# PR9013.net
KiCad netlist of a schematic drawn in EAGLE
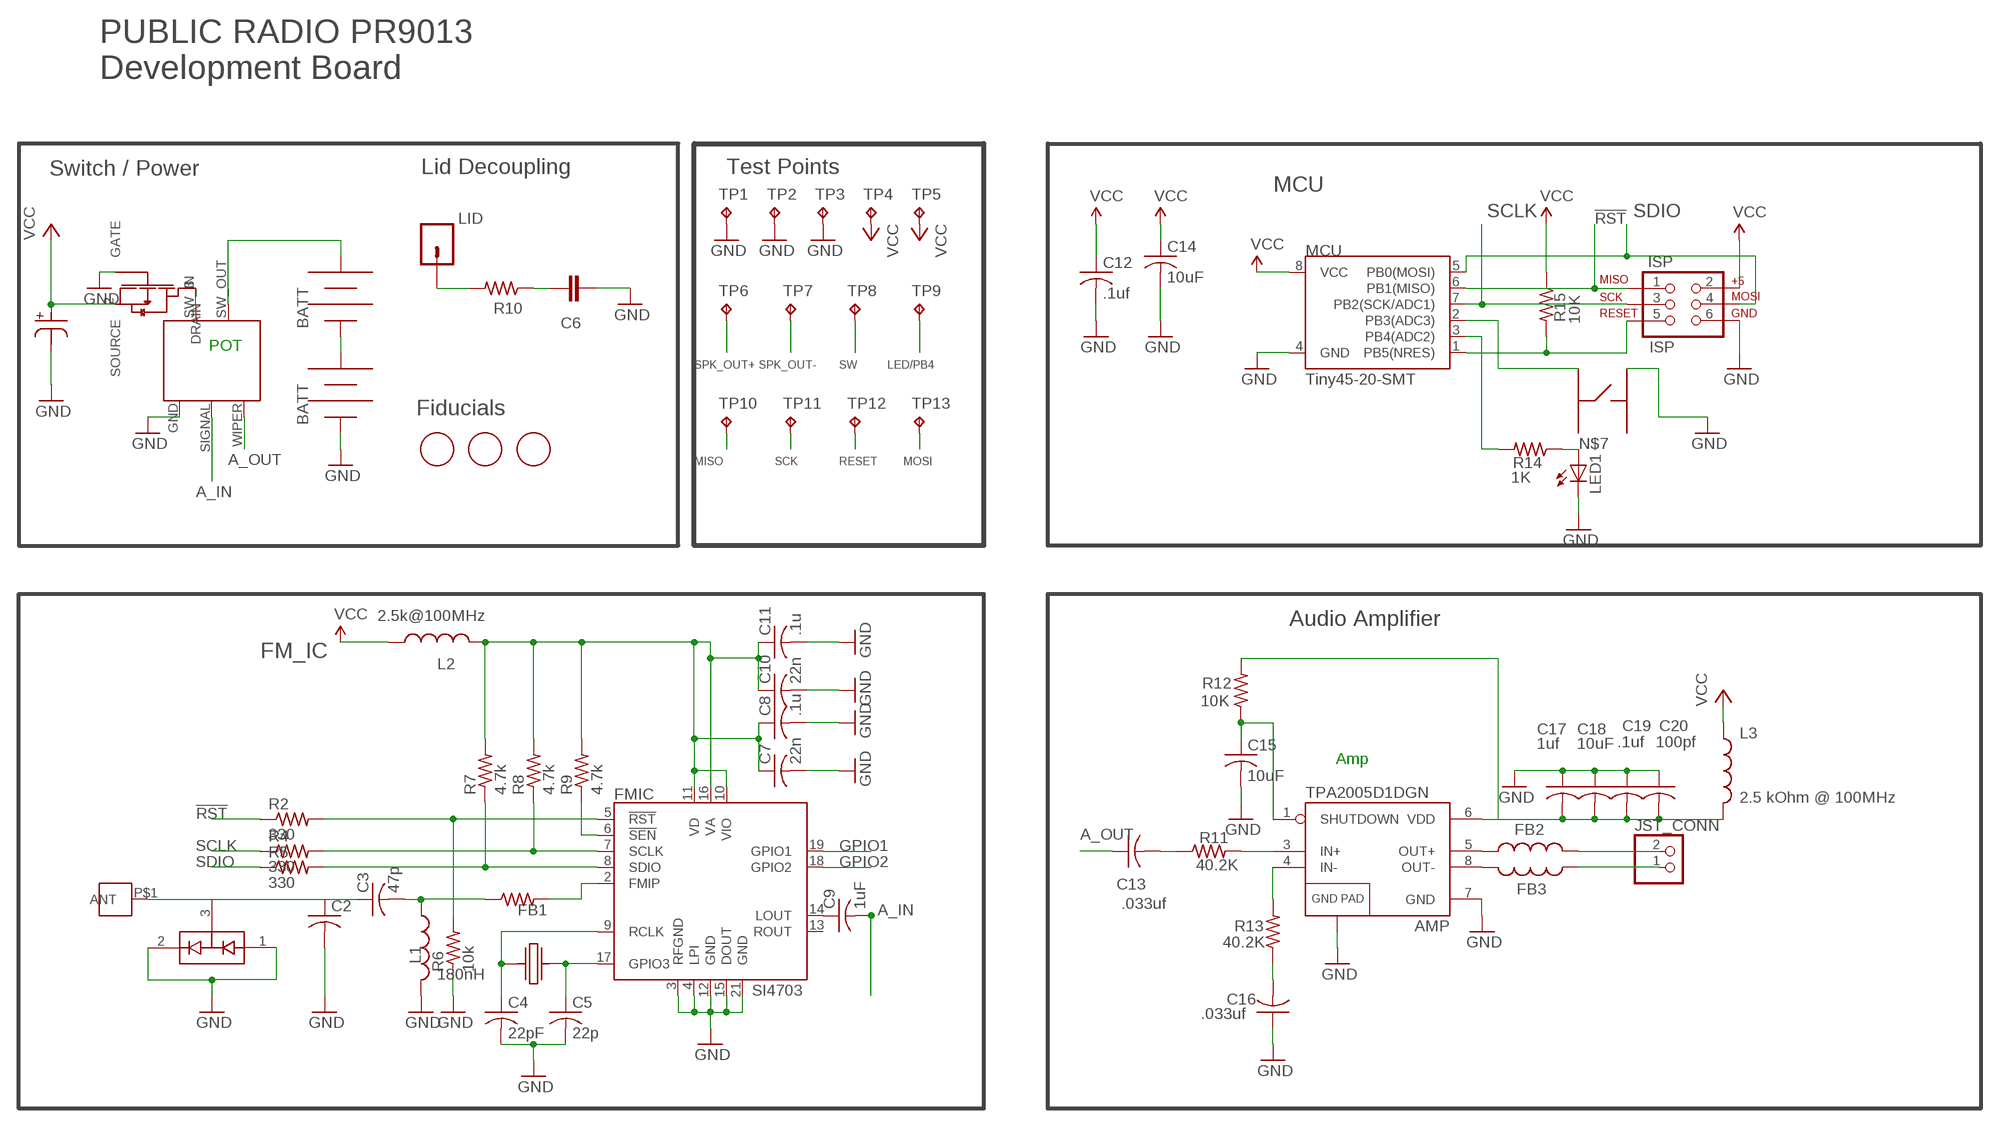
[diagram p0: schematic, sheet 1]

(export (version "E")
  (design (tool "Eeschema 10.0.6"))
  (components
    (comp (ref "AMP")
      (value "TPA2005D1DGN")
      (footprint "eagle-import:POWER-SOP8")
      (libsource (lib "eagle-import") (part "TPA2005D1DGN"))
    )
    (comp (ref "C1")
      (value "220uF")
      (footprint "eagle-import:NICHICON_SERIESUD")
      (libsource (lib "eagle-import") (part "NICHICON_SERIESUD"))
    )
    (comp (ref "C2")
      (value "C-USC0402")
      (footprint "eagle-import:C0402")
      (libsource (lib "eagle-import") (part "C-USC0402"))
    )
    (comp (ref "C3")
      (value "47p")
      (footprint "eagle-import:C0402")
      (libsource (lib "eagle-import") (part "C-USC0402"))
    )
    (comp (ref "C4")
      (value "22pF")
      (footprint "eagle-import:C0402")
      (libsource (lib "eagle-import") (part "C-USC0402"))
    )
    (comp (ref "C5")
      (value "22p")
      (footprint "eagle-import:C0402")
      (libsource (lib "eagle-import") (part "C-USC0402"))
    )
    (comp (ref "C6")
      (value "CAP0805")
      (footprint "eagle-import:0805")
      (libsource (lib "eagle-import") (part "CAP0805"))
    )
    (comp (ref "C7")
      (value "22n")
      (footprint "eagle-import:C0402")
      (libsource (lib "eagle-import") (part "C-USC0402"))
    )
    (comp (ref "C8")
      (value ".1u")
      (footprint "eagle-import:C0402")
      (libsource (lib "eagle-import") (part "C-USC0402"))
    )
    (comp (ref "C9")
      (value "1uF")
      (footprint "eagle-import:C0402")
      (libsource (lib "eagle-import") (part "C-USC0402"))
    )
    (comp (ref "C10")
      (value "22n")
      (footprint "eagle-import:C0402")
      (libsource (lib "eagle-import") (part "C-USC0402"))
    )
    (comp (ref "C11")
      (value ".1u")
      (footprint "eagle-import:C0402")
      (libsource (lib "eagle-import") (part "C-USC0402"))
    )
    (comp (ref "C12")
      (value ".1uf")
      (footprint "eagle-import:C0402")
      (libsource (lib "eagle-import") (part "C-USC0402"))
    )
    (comp (ref "C13")
      (value ".033uf")
      (footprint "eagle-import:C0402")
      (libsource (lib "eagle-import") (part "C-USC0402"))
    )
    (comp (ref "C14")
      (value "10uF")
      (footprint "eagle-import:C0603")
      (libsource (lib "eagle-import") (part "C-USC0603"))
    )
    (comp (ref "C15")
      (value "10uF")
      (footprint "eagle-import:C0603")
      (libsource (lib "eagle-import") (part "C-USC0603"))
    )
    (comp (ref "C16")
      (value ".033uf")
      (footprint "eagle-import:C0402")
      (libsource (lib "eagle-import") (part "C-USC0402"))
    )
    (comp (ref "C17")
      (value "1uf")
      (footprint "eagle-import:C0402")
      (libsource (lib "eagle-import") (part "C-USC0402"))
    )
    (comp (ref "C18")
      (value "10uF")
      (footprint "eagle-import:C0603")
      (libsource (lib "eagle-import") (part "C-USC0603"))
    )
    (comp (ref "C19")
      (value ".1uf")
      (footprint "eagle-import:C0402")
      (libsource (lib "eagle-import") (part "C-USC0402"))
    )
    (comp (ref "C20")
      (value "100pf")
      (footprint "eagle-import:C0402")
      (libsource (lib "eagle-import") (part "C-USC0402"))
    )
    (comp (ref "D1")
      (value "BAV99")
      (footprint "eagle-import:SOT23")
      (libsource (lib "eagle-import") (part "BAV99"))
    )
    (comp (ref "FB1")
      (value "R-US_R0402")
      (footprint "eagle-import:R0402")
      (libsource (lib "eagle-import") (part "R-US_R0402"))
    )
    (comp (ref "FB2")
      (value "INDUCTOR0603")
      (footprint "eagle-import:0603")
      (libsource (lib "eagle-import") (part "INDUCTOR0603"))
    )
    (comp (ref "FB3")
      (value "INDUCTOR0603")
      (footprint "eagle-import:0603")
      (libsource (lib "eagle-import") (part "INDUCTOR0603"))
    )
    (comp (ref "FET1")
      (value "SI2333DDS")
      (footprint "eagle-import:SI2333DDS")
      (libsource (lib "eagle-import") (part "SI2333DDS"))
    )
    (comp (ref "FMIC")
      (value "SI4703")
      (footprint "eagle-import:SPARKFUN_SI470X")
      (libsource (lib "eagle-import") (part "SPARKFUN_SI470X"))
    )
    (comp (ref "ISP")
      (value "ISP")
      (footprint "eagle-import:2X3-NS")
      (libsource (lib "eagle-import") (part "AVR_SPI_PRG_6NS"))
    )
    (comp (ref "J1")
      (value "M3_SCREW_POST")
      (footprint "eagle-import:M3_SCREW_POST")
      (libsource (lib "eagle-import") (part "M3_SCREW_POST"))
    )
    (comp (ref "JP5")
      (value "BK-92_MPD_AA_BATT_CLIP")
      (footprint "eagle-import:BK-92_MPD_AA_BATT_CLIP")
      (libsource (lib "eagle-import") (part "BK-92_MPD_AA_BATT_CLIP"))
    )
    (comp (ref "JP6")
      (value "BK-92_MPD_AA_BATT_CLIP")
      (footprint "eagle-import:BK-92_MPD_AA_BATT_CLIP")
      (libsource (lib "eagle-import") (part "BK-92_MPD_AA_BATT_CLIP"))
    )
    (comp (ref "JST_CONN")
      (value "JST_2PIN-SMT-RA")
      (footprint "eagle-import:JST-PH-2-SMT-RA")
      (libsource (lib "eagle-import") (part "JST_2PIN-SMT-RA"))
    )
    (comp (ref "L1")
      (value "180nH")
      (footprint "eagle-import:0603")
      (libsource (lib "eagle-import") (part "INDUCTOR0603"))
    )
    (comp (ref "L2")
      (value "2.5k@100MHz")
      (footprint "eagle-import:0603")
      (libsource (lib "eagle-import") (part "INDUCTOR0603"))
    )
    (comp (ref "L3")
      (value "2.5 kOhm @ 100MHz")
      (footprint "eagle-import:0603")
      (libsource (lib "eagle-import") (part "INDUCTOR0603"))
    )
    (comp (ref "LED1")
      (value "LEDSML0603")
      (footprint "eagle-import:SML0603")
      (libsource (lib "eagle-import") (part "LEDSML0603"))
    )
    (comp (ref "LID")
      (value "M01PTH")
      (footprint "eagle-import:1X01")
      (libsource (lib "eagle-import") (part "M01PTH"))
    )
    (comp (ref "MCU")
      (value "Tiny45-20-SMT")
      (footprint "eagle-import:SO08-EIAJ")
      (libsource (lib "eagle-import") (part "ATTINY45TINY85-20-SMT"))
    )
    (comp (ref "R1")
      (value "RV170SF_TAIWANA_POT_SW")
      (footprint "eagle-import:RV170SF_TAIWANA_POT_SW")
      (libsource (lib "eagle-import") (part "RV170SF_TAIWANA_POT_SW"))
    )
    (comp (ref "R2")
      (value "330")
      (footprint "eagle-import:R0402")
      (libsource (lib "eagle-import") (part "R-US_R0402"))
    )
    (comp (ref "R4")
      (value "330")
      (footprint "eagle-import:R0402")
      (libsource (lib "eagle-import") (part "R-US_R0402"))
    )
    (comp (ref "R5")
      (value "330")
      (footprint "eagle-import:R0402")
      (libsource (lib "eagle-import") (part "R-US_R0402"))
    )
    (comp (ref "R6")
      (value "10k")
      (footprint "eagle-import:R0402")
      (libsource (lib "eagle-import") (part "R-US_R0402"))
    )
    (comp (ref "R7")
      (value "4.7k")
      (footprint "eagle-import:R0402")
      (libsource (lib "eagle-import") (part "R-US_R0402"))
    )
    (comp (ref "R8")
      (value "4.7k")
      (footprint "eagle-import:R0402")
      (libsource (lib "eagle-import") (part "R-US_R0402"))
    )
    (comp (ref "R9")
      (value "4.7k")
      (footprint "eagle-import:R0402")
      (libsource (lib "eagle-import") (part "R-US_R0402"))
    )
    (comp (ref "R10")
      (value "R-US_R0402")
      (footprint "eagle-import:R0402")
      (libsource (lib "eagle-import") (part "R-US_R0402"))
    )
    (comp (ref "R11")
      (value "40.2K")
      (footprint "eagle-import:R0402")
      (libsource (lib "eagle-import") (part "R-US_R0402"))
    )
    (comp (ref "R12")
      (value "10K")
      (footprint "eagle-import:R0402")
      (libsource (lib "eagle-import") (part "R-US_R0402"))
    )
    (comp (ref "R13")
      (value "40.2K")
      (footprint "eagle-import:R0402")
      (libsource (lib "eagle-import") (part "R-US_R0402"))
    )
    (comp (ref "R14")
      (value "1K")
      (footprint "eagle-import:R0402")
      (libsource (lib "eagle-import") (part "R-US_R0402"))
    )
    (comp (ref "R15")
      (value "10K")
      (footprint "eagle-import:R0402")
      (libsource (lib "eagle-import") (part "R-US_R0402"))
    )
    (comp (ref "TP1")
      (value "TPTP14R")
      (footprint "eagle-import:TP14R")
      (libsource (lib "eagle-import") (part "TPTP14R"))
    )
    (comp (ref "TP2")
      (value "TPTP14R")
      (footprint "eagle-import:TP14R")
      (libsource (lib "eagle-import") (part "TPTP14R"))
    )
    (comp (ref "TP3")
      (value "TPTP14R")
      (footprint "eagle-import:TP14R")
      (libsource (lib "eagle-import") (part "TPTP14R"))
    )
    (comp (ref "TP4")
      (value "TPTP14R")
      (footprint "eagle-import:TP14R")
      (libsource (lib "eagle-import") (part "TPTP14R"))
    )
    (comp (ref "TP5")
      (value "TPTP14R")
      (footprint "eagle-import:TP14R")
      (libsource (lib "eagle-import") (part "TPTP14R"))
    )
    (comp (ref "TP6")
      (value "TPTP14R")
      (footprint "eagle-import:TP14R")
      (libsource (lib "eagle-import") (part "TPTP14R"))
    )
    (comp (ref "TP7")
      (value "TPTP14R")
      (footprint "eagle-import:TP14R")
      (libsource (lib "eagle-import") (part "TPTP14R"))
    )
    (comp (ref "TP8")
      (value "TPTP14R")
      (footprint "eagle-import:TP14R")
      (libsource (lib "eagle-import") (part "TPTP14R"))
    )
    (comp (ref "TP9")
      (value "TPTP14R")
      (footprint "eagle-import:TP14R")
      (libsource (lib "eagle-import") (part "TPTP14R"))
    )
    (comp (ref "TP10")
      (value "TPTP14R")
      (footprint "eagle-import:TP14R")
      (libsource (lib "eagle-import") (part "TPTP14R"))
    )
    (comp (ref "TP11")
      (value "TPTP14R")
      (footprint "eagle-import:TP14R")
      (libsource (lib "eagle-import") (part "TPTP14R"))
    )
    (comp (ref "TP12")
      (value "TPTP14R")
      (footprint "eagle-import:TP14R")
      (libsource (lib "eagle-import") (part "TPTP14R"))
    )
    (comp (ref "TP13")
      (value "TPTP14R")
      (footprint "eagle-import:TP14R")
      (libsource (lib "eagle-import") (part "TPTP14R"))
    )
    (comp (ref "U$1")
      (value "C&KPTS6465")
      (footprint "eagle-import:C&K_TACTILE_SWITCH")
      (libsource (lib "eagle-import") (part "C&KPTS6465"))
    )
    (comp (ref "U$3")
      (value "FIDUCIAL")
      (footprint "eagle-import:FIDUCIAL_1MM")
      (libsource (lib "eagle-import") (part "FIDUCIAL"))
    )
    (comp (ref "U$4")
      (value "FIDUCIAL")
      (footprint "eagle-import:FIDUCIAL_1MM")
      (libsource (lib "eagle-import") (part "FIDUCIAL"))
    )
    (comp (ref "U$5")
      (value "FIDUCIAL")
      (footprint "eagle-import:FIDUCIAL_1MM")
      (libsource (lib "eagle-import") (part "FIDUCIAL"))
    )
    (comp (ref "U$6")
      (value "ABS25XTAL")
      (footprint "eagle-import:ABS25XTAL")
      (libsource (lib "eagle-import") (part "ABS25XTAL"))
    )
  )
  (nets
    (net (code "1") (name "/A_IN") (class "Default")
      (node (ref "C9") (pin "2") (pinfunction "2_2") (pintype "passive"))
      (node (ref "R1") (pin "SIGNAL") (pinfunction "SIGNAL_SIGNAL") (pintype "bidirectional"))
    )
    (net (code "2") (name "/A_OUT") (class "Default")
      (node (ref "C13") (pin "1") (pinfunction "1_1") (pintype "passive"))
      (node (ref "R1") (pin "WIPER") (pinfunction "WIPER_WIPER") (pintype "bidirectional"))
    )
    (net (code "3") (name "/GPIO1") (class "Default")
      (node (ref "FMIC") (pin "19") (pinfunction "GPIO1_19") (pintype "bidirectional"))
    )
    (net (code "4") (name "/GPIO2") (class "Default")
      (node (ref "FMIC") (pin "18") (pinfunction "GPIO2_18") (pintype "bidirectional"))
    )
    (net (code "5") (name "/LED{slash}PB4") (class "Default")
      (node (ref "MCU") (pin "3") (pinfunction "PB4(ADC2)_3") (pintype "bidirectional"))
      (node (ref "R14") (pin "2") (pinfunction "2_2") (pintype "passive"))
      (node (ref "TP9") (pin "TP") (pinfunction "TP_TP") (pintype "input"))
    )
    (net (code "6") (name "/N$7") (class "Default")
      (node (ref "LED1") (pin "A") (pinfunction "A_A") (pintype "passive"))
      (node (ref "R14") (pin "1") (pinfunction "1_1") (pintype "passive"))
    )
    (net (code "7") (name "/RESET") (class "Default")
      (node (ref "ISP") (pin "5") (pinfunction "5_5") (pintype "passive"))
      (node (ref "MCU") (pin "1") (pinfunction "PB5(NRES)_1") (pintype "bidirectional"))
      (node (ref "R15") (pin "2") (pinfunction "2_2") (pintype "passive"))
      (node (ref "TP12") (pin "TP") (pinfunction "TP_TP") (pintype "input"))
    )
    (net (code "8") (name "/SCLK") (class "Default")
      (node (ref "ISP") (pin "3") (pinfunction "3_3") (pintype "passive"))
      (node (ref "MCU") (pin "7") (pinfunction "PB2(SCK/ADC1)_7") (pintype "bidirectional"))
      (node (ref "R4") (pin "1") (pinfunction "1_1") (pintype "passive"))
      (node (ref "TP11") (pin "TP") (pinfunction "TP_TP") (pintype "input"))
    )
    (net (code "9") (name "/SDIO") (class "Default")
      (node (ref "ISP") (pin "4") (pinfunction "4_4") (pintype "passive"))
      (node (ref "MCU") (pin "5") (pinfunction "PB0(MOSI)_5") (pintype "bidirectional"))
      (node (ref "R5") (pin "1") (pinfunction "1_1") (pintype "passive"))
      (node (ref "TP13") (pin "TP") (pinfunction "TP_TP") (pintype "input"))
    )
    (net (code "10") (name "/SPK_OUT+") (class "Default")
      (node (ref "FB2") (pin "2") (pinfunction "2_2") (pintype "passive"))
      (node (ref "JST_CONN") (pin "2") (pinfunction "1_2") (pintype "passive"))
      (node (ref "TP6") (pin "TP") (pinfunction "TP_TP") (pintype "input"))
    )
    (net (code "11") (name "/SPK_OUT-") (class "Default")
      (node (ref "FB3") (pin "1") (pinfunction "1_1") (pintype "passive"))
      (node (ref "JST_CONN") (pin "1") (pinfunction "2_1") (pintype "passive"))
      (node (ref "TP7") (pin "TP") (pinfunction "TP_TP") (pintype "input"))
    )
    (net (code "12") (name "/SW") (class "Default")
      (node (ref "MCU") (pin "2") (pinfunction "PB3(ADC3)_2") (pintype "bidirectional"))
      (node (ref "TP8") (pin "TP") (pinfunction "TP_TP") (pintype "input"))
      (node (ref "U$1") (pin "P$3") (pinfunction "P$3_P$3") (pintype "bidirectional"))
    )
    (net (code "13") (name "/~{RST}") (class "Default")
      (node (ref "ISP") (pin "1") (pinfunction "1_1") (pintype "passive"))
      (node (ref "MCU") (pin "6") (pinfunction "PB1(MISO)_6") (pintype "bidirectional"))
      (node (ref "R2") (pin "1") (pinfunction "1_1") (pintype "passive"))
      (node (ref "TP10") (pin "TP") (pinfunction "TP_TP") (pintype "input"))
    )
    (net (code "14") (name "GND") (class "Default")
      (node (ref "AMP") (pin "7") (pinfunction "GND_7") (pintype "power_in"))
      (node (ref "AMP") (pin "9") (pinfunction "GND_9") (pintype "power_in"))
      (node (ref "C1") (pin "P$2") (pinfunction "P$2_P$2") (pintype "bidirectional"))
      (node (ref "C10") (pin "2") (pinfunction "2_2") (pintype "passive"))
      (node (ref "C11") (pin "2") (pinfunction "2_2") (pintype "passive"))
      (node (ref "C12") (pin "2") (pinfunction "2_2") (pintype "passive"))
      (node (ref "C14") (pin "2") (pinfunction "2_2") (pintype "passive"))
      (node (ref "C15") (pin "2") (pinfunction "2_2") (pintype "passive"))
      (node (ref "C16") (pin "1") (pinfunction "1_1") (pintype "passive"))
      (node (ref "C17") (pin "1") (pinfunction "1_1") (pintype "passive"))
      (node (ref "C18") (pin "1") (pinfunction "1_1") (pintype "passive"))
      (node (ref "C19") (pin "1") (pinfunction "1_1") (pintype "passive"))
      (node (ref "C2") (pin "2") (pinfunction "2_2") (pintype "passive"))
      (node (ref "C20") (pin "1") (pinfunction "1_1") (pintype "passive"))
      (node (ref "C4") (pin "2") (pinfunction "2_2") (pintype "passive"))
      (node (ref "C5") (pin "2") (pinfunction "2_2") (pintype "passive"))
      (node (ref "C6") (pin "2") (pinfunction "2_2") (pintype "passive"))
      (node (ref "C7") (pin "2") (pinfunction "2_2") (pintype "passive"))
      (node (ref "C8") (pin "2") (pinfunction "2_2") (pintype "passive"))
      (node (ref "D1") (pin "1") (pinfunction "A1_1") (pintype "bidirectional"))
      (node (ref "D1") (pin "2") (pinfunction "C2_2") (pintype "bidirectional"))
      (node (ref "FET1") (pin "1") (pinfunction "GATE_1") (pintype "bidirectional"))
      (node (ref "FMIC") (pin "12") (pinfunction "GND_12") (pintype "bidirectional"))
      (node (ref "FMIC") (pin "15") (pinfunction "DOUT_15") (pintype "bidirectional"))
      (node (ref "FMIC") (pin "21") (pinfunction "GND_21") (pintype "bidirectional"))
      (node (ref "FMIC") (pin "3") (pinfunction "RFGND_3") (pintype "bidirectional"))
      (node (ref "FMIC") (pin "4") (pinfunction "LPI_4") (pintype "bidirectional"))
      (node (ref "ISP") (pin "6") (pinfunction "6_6") (pintype "passive"))
      (node (ref "JP6") (pin "NEG") (pinfunction "NEG_NEG") (pintype "bidirectional"))
      (node (ref "JP6") (pin "NEG@2") (pinfunction "NEG_NEG@2") (pintype "bidirectional"))
      (node (ref "L1") (pin "2") (pinfunction "2_2") (pintype "passive"))
      (node (ref "LED1") (pin "C") (pinfunction "C_C") (pintype "passive"))
      (node (ref "MCU") (pin "4") (pinfunction "GND_4") (pintype "bidirectional"))
      (node (ref "R1") (pin "GND") (pinfunction "GND_GND") (pintype "bidirectional"))
      (node (ref "R6") (pin "1") (pinfunction "1_1") (pintype "passive"))
      (node (ref "TP1") (pin "TP") (pinfunction "TP_TP") (pintype "input"))
      (node (ref "TP2") (pin "TP") (pinfunction "TP_TP") (pintype "input"))
      (node (ref "TP3") (pin "TP") (pinfunction "TP_TP") (pintype "input"))
      (node (ref "U$1") (pin "P$1") (pinfunction "P$1_P$1") (pintype "bidirectional"))
    )
    (net (code "15") (name "Net-(AMP-IN+)") (class "Default")
      (node (ref "AMP") (pin "3") (pinfunction "IN+_3") (pintype "bidirectional"))
      (node (ref "R11") (pin "2") (pinfunction "2_2") (pintype "passive"))
    )
    (net (code "16") (name "Net-(AMP-IN-)") (class "Default")
      (node (ref "AMP") (pin "4") (pinfunction "IN-_4") (pintype "bidirectional"))
      (node (ref "R13") (pin "2") (pinfunction "2_2") (pintype "passive"))
    )
    (net (code "17") (name "Net-(AMP-OUT+)") (class "Default")
      (node (ref "AMP") (pin "5") (pinfunction "OUT+_5") (pintype "bidirectional"))
      (node (ref "FB2") (pin "1") (pinfunction "1_1") (pintype "passive"))
    )
    (net (code "18") (name "Net-(AMP-OUT-)") (class "Default")
      (node (ref "AMP") (pin "8") (pinfunction "OUT-_8") (pintype "bidirectional"))
      (node (ref "FB3") (pin "2") (pinfunction "2_2") (pintype "passive"))
    )
    (net (code "19") (name "Net-(AMP-SHUTDOWN)") (class "Default")
      (node (ref "AMP") (pin "1") (pinfunction "SHUTDOWN_1") (pintype "input"))
      (node (ref "C15") (pin "1") (pinfunction "1_1") (pintype "passive"))
      (node (ref "R12") (pin "1") (pinfunction "1_1") (pintype "passive"))
    )
    (net (code "20") (name "Net-(AMP-VDD)") (class "Default")
      (node (ref "AMP") (pin "6") (pinfunction "VDD_6") (pintype "power_in"))
      (node (ref "C17") (pin "2") (pinfunction "2_2") (pintype "passive"))
      (node (ref "C18") (pin "2") (pinfunction "2_2") (pintype "passive"))
      (node (ref "C19") (pin "2") (pinfunction "2_2") (pintype "passive"))
      (node (ref "C20") (pin "2") (pinfunction "2_2") (pintype "passive"))
      (node (ref "L3") (pin "2") (pinfunction "2_2") (pintype "passive"))
      (node (ref "R12") (pin "2") (pinfunction "2_2") (pintype "passive"))
    )
    (net (code "21") (name "Net-(C3-Pad2)") (class "Default")
      (node (ref "C3") (pin "2") (pinfunction "2_2") (pintype "passive"))
      (node (ref "FB1") (pin "1") (pinfunction "1_1") (pintype "passive"))
      (node (ref "L1") (pin "1") (pinfunction "1_1") (pintype "passive"))
    )
    (net (code "22") (name "Net-(C6-Pad1)") (class "Default")
      (node (ref "C6") (pin "1") (pinfunction "1_1") (pintype "passive"))
      (node (ref "R10") (pin "1") (pinfunction "1_1") (pintype "passive"))
    )
    (net (code "23") (name "Net-(C13-Pad2)") (class "Default")
      (node (ref "C13") (pin "2") (pinfunction "2_2") (pintype "passive"))
      (node (ref "R11") (pin "1") (pinfunction "1_1") (pintype "passive"))
    )
    (net (code "24") (name "Net-(C16-Pad2)") (class "Default")
      (node (ref "C16") (pin "2") (pinfunction "2_2") (pintype "passive"))
      (node (ref "R13") (pin "1") (pinfunction "1_1") (pintype "passive"))
    )
    (net (code "25") (name "Net-(D1-COM)") (class "Default")
      (node (ref "C2") (pin "1") (pinfunction "1_1") (pintype "passive"))
      (node (ref "C3") (pin "1") (pinfunction "1_1") (pintype "passive"))
      (node (ref "D1") (pin "3") (pinfunction "COM_3") (pintype "bidirectional"))
      (node (ref "J1") (pin "P$1") (pinfunction "ANT_P$1") (pintype "bidirectional"))
    )
    (net (code "26") (name "Net-(FET1-DRAIN)") (class "Default")
      (node (ref "FET1") (pin "3") (pinfunction "DRAIN_3") (pintype "bidirectional"))
      (node (ref "R1") (pin "SW_IN") (pinfunction "SW_IN_SW_IN") (pintype "bidirectional"))
    )
    (net (code "27") (name "Net-(FMIC-FMIP)") (class "Default")
      (node (ref "FB1") (pin "2") (pinfunction "2_2") (pintype "passive"))
      (node (ref "FMIC") (pin "2") (pinfunction "FMIP_2") (pintype "bidirectional"))
    )
    (net (code "28") (name "Net-(FMIC-GPIO3)") (class "Default")
      (node (ref "C5") (pin "1") (pinfunction "1_1") (pintype "passive"))
      (node (ref "FMIC") (pin "17") (pinfunction "GPIO3_17") (pintype "bidirectional"))
      (node (ref "U$6") (pin "P$1") (pinfunction "P$1_P$1") (pintype "bidirectional"))
    )
    (net (code "29") (name "Net-(FMIC-LOUT)") (class "Default")
      (node (ref "C9") (pin "1") (pinfunction "1_1") (pintype "passive"))
      (node (ref "FMIC") (pin "14") (pinfunction "LOUT_14") (pintype "bidirectional"))
    )
    (net (code "30") (name "Net-(FMIC-RCLK)") (class "Default")
      (node (ref "C4") (pin "1") (pinfunction "1_1") (pintype "passive"))
      (node (ref "FMIC") (pin "9") (pinfunction "RCLK_9") (pintype "bidirectional"))
      (node (ref "U$6") (pin "P$4") (pinfunction "P$4_P$4") (pintype "bidirectional"))
    )
    (net (code "31") (name "Net-(FMIC-SCLK)") (class "Default")
      (node (ref "FMIC") (pin "7") (pinfunction "SCLK_7") (pintype "bidirectional"))
      (node (ref "R4") (pin "2") (pinfunction "2_2") (pintype "passive"))
      (node (ref "R8") (pin "1") (pinfunction "1_1") (pintype "passive"))
    )
    (net (code "32") (name "Net-(FMIC-SDIO)") (class "Default")
      (node (ref "FMIC") (pin "8") (pinfunction "SDIO_8") (pintype "bidirectional"))
      (node (ref "R5") (pin "2") (pinfunction "2_2") (pintype "passive"))
      (node (ref "R7") (pin "1") (pinfunction "1_1") (pintype "passive"))
    )
    (net (code "33") (name "Net-(FMIC-VA)") (class "Default")
      (node (ref "C10") (pin "1") (pinfunction "1_1") (pintype "passive"))
      (node (ref "C11") (pin "1") (pinfunction "1_1") (pintype "passive"))
      (node (ref "C7") (pin "1") (pinfunction "1_1") (pintype "passive"))
      (node (ref "C8") (pin "1") (pinfunction "1_1") (pintype "passive"))
      (node (ref "FMIC") (pin "10") (pinfunction "VIO_10") (pintype "bidirectional"))
      (node (ref "FMIC") (pin "11") (pinfunction "VD_11") (pintype "bidirectional"))
      (node (ref "FMIC") (pin "16") (pinfunction "VA_16") (pintype "bidirectional"))
      (node (ref "L2") (pin "2") (pinfunction "2_2") (pintype "passive"))
      (node (ref "R7") (pin "2") (pinfunction "2_2") (pintype "passive"))
      (node (ref "R8") (pin "2") (pinfunction "2_2") (pintype "passive"))
      (node (ref "R9") (pin "2") (pinfunction "2_2") (pintype "passive"))
    )
    (net (code "34") (name "Net-(FMIC-~{RST})") (class "Default")
      (node (ref "FMIC") (pin "5") (pinfunction "~{RST}_5") (pintype "bidirectional"))
      (node (ref "R2") (pin "2") (pinfunction "2_2") (pintype "passive"))
      (node (ref "R6") (pin "2") (pinfunction "2_2") (pintype "passive"))
    )
    (net (code "35") (name "Net-(FMIC-~{SEN})") (class "Default")
      (node (ref "FMIC") (pin "6") (pinfunction "~{SEN}_6") (pintype "bidirectional"))
      (node (ref "R9") (pin "1") (pinfunction "1_1") (pintype "passive"))
    )
    (net (code "36") (name "Net-(JP5-NEG-PadNEG@2)") (class "Default")
      (node (ref "JP5") (pin "NEG") (pinfunction "NEG_NEG") (pintype "bidirectional"))
      (node (ref "JP5") (pin "NEG@2") (pinfunction "NEG_NEG@2") (pintype "bidirectional"))
      (node (ref "JP6") (pin "POS") (pinfunction "POS_POS") (pintype "bidirectional"))
      (node (ref "JP6") (pin "POS@2") (pinfunction "POS_POS@2") (pintype "bidirectional"))
    )
    (net (code "37") (name "Net-(JP5-POS-PadPOS@2)") (class "Default")
      (node (ref "JP5") (pin "POS") (pinfunction "POS_POS") (pintype "bidirectional"))
      (node (ref "JP5") (pin "POS@2") (pinfunction "POS_POS@2") (pintype "bidirectional"))
      (node (ref "R1") (pin "SW_OUT") (pinfunction "SW_OUT_SW_OUT") (pintype "bidirectional"))
    )
    (net (code "38") (name "Net-(LID-Pad1)") (class "Default")
      (node (ref "LID") (pin "1") (pinfunction "1_1") (pintype "passive"))
      (node (ref "R10") (pin "2") (pinfunction "2_2") (pintype "passive"))
    )
    (net (code "39") (name "VCC") (class "Default")
      (node (ref "C1") (pin "P$1") (pinfunction "P$1_P$1") (pintype "bidirectional"))
      (node (ref "C12") (pin "1") (pinfunction "1_1") (pintype "passive"))
      (node (ref "C14") (pin "1") (pinfunction "1_1") (pintype "passive"))
      (node (ref "FET1") (pin "2") (pinfunction "SOURCE_2") (pintype "bidirectional"))
      (node (ref "ISP") (pin "2") (pinfunction "2_2") (pintype "passive"))
      (node (ref "L2") (pin "1") (pinfunction "1_1") (pintype "passive"))
      (node (ref "L3") (pin "1") (pinfunction "1_1") (pintype "passive"))
      (node (ref "MCU") (pin "8") (pinfunction "VCC_8") (pintype "bidirectional"))
      (node (ref "R15") (pin "1") (pinfunction "1_1") (pintype "passive"))
      (node (ref "TP4") (pin "TP") (pinfunction "TP_TP") (pintype "input"))
      (node (ref "TP5") (pin "TP") (pinfunction "TP_TP") (pintype "input"))
    )
    (net (code "40") (name "unconnected-(FMIC-ROUT-Pad13)") (class "Default")
      (node (ref "FMIC") (pin "13") (pinfunction "ROUT_13") (pintype "bidirectional"))
    )
    (net (code "41") (name "unconnected-(U$1-PadP$2)") (class "Default")
      (node (ref "U$1") (pin "P$2") (pinfunction "P$2_P$2") (pintype "bidirectional"))
    )
    (net (code "42") (name "unconnected-(U$1-PadP$4)") (class "Default")
      (node (ref "U$1") (pin "P$4") (pinfunction "P$4_P$4") (pintype "bidirectional"))
    )
  )
)
